# AS5047P.net
KiCad netlist of a schematic drawn in EAGLE
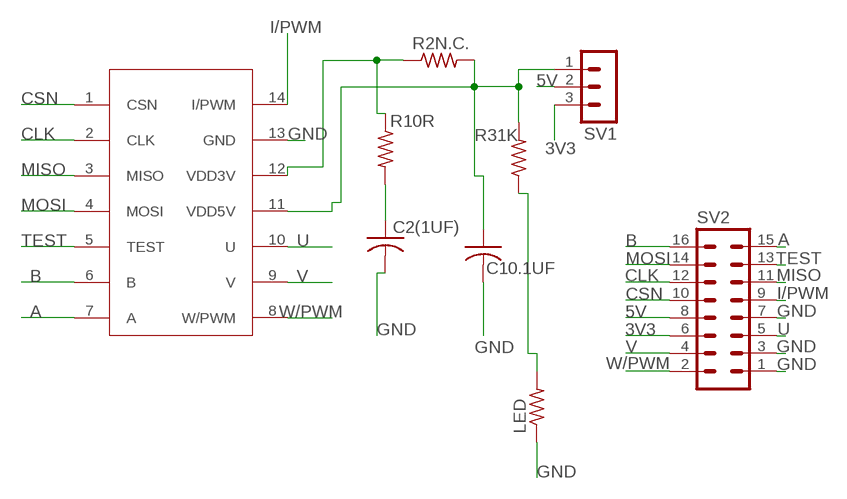
[diagram p0: schematic, sheet 1]

(export (version "E")
  (design (tool "Eeschema 10.0.6"))
  (components
    (comp (ref "C2(1UF)")
      (value "C-USC1206")
      (footprint "eagle-import:C1206")
      (libsource (lib "eagle-import") (part "C-USC1206"))
    )
    (comp (ref "C10.1UF")
      (value "C-USC1206")
      (footprint "eagle-import:C1206")
      (libsource (lib "eagle-import") (part "C-USC1206"))
    )
    (comp (ref "LED")
      (value "R-US_R1206")
      (footprint "eagle-import:R1206")
      (libsource (lib "eagle-import") (part "R-US_R1206"))
    )
    (comp (ref "R2N.C.")
      (value "R-US_R1206")
      (footprint "eagle-import:R1206")
      (libsource (lib "eagle-import") (part "R-US_R1206"))
    )
    (comp (ref "R10R")
      (value "R-US_R1206")
      (footprint "eagle-import:R1206")
      (libsource (lib "eagle-import") (part "R-US_R1206"))
    )
    (comp (ref "R31K")
      (value "R-US_R1206")
      (footprint "eagle-import:R1206")
      (libsource (lib "eagle-import") (part "R-US_R1206"))
    )
    (comp (ref "SV1")
      (value "MA03-1")
      (footprint "eagle-import:MA03-1")
      (libsource (lib "eagle-import") (part "MA03-1"))
    )
    (comp (ref "SV2")
      (value "MA08-2")
      (footprint "eagle-import:MA08-2")
      (libsource (lib "eagle-import") (part "MA08-2"))
    )
    (comp (ref "U$1")
      (value "AS5047")
      (footprint "eagle-import:SOP65P640X110-14N")
      (libsource (lib "eagle-import") (part "AS5047"))
    )
  )
  (nets
    (net (code "1") (name "/3V3") (class "Default")
      (node (ref "SV1") (pin "3") (pinfunction "3_3") (pintype "passive"))
      (node (ref "SV2") (pin "6") (pinfunction "6_6") (pintype "passive"))
    )
    (net (code "2") (name "/5V") (class "Default")
      (node (ref "SV1") (pin "2") (pinfunction "2_2") (pintype "passive"))
      (node (ref "SV2") (pin "8") (pinfunction "8_8") (pintype "passive"))
    )
    (net (code "3") (name "/A") (class "Default")
      (node (ref "SV2") (pin "15") (pinfunction "15_15") (pintype "passive"))
      (node (ref "U$1") (pin "7") (pinfunction "A_7") (pintype "bidirectional"))
    )
    (net (code "4") (name "/B") (class "Default")
      (node (ref "SV2") (pin "16") (pinfunction "16_16") (pintype "passive"))
      (node (ref "U$1") (pin "6") (pinfunction "B_6") (pintype "bidirectional"))
    )
    (net (code "5") (name "/CLK") (class "Default")
      (node (ref "SV2") (pin "12") (pinfunction "12_12") (pintype "passive"))
      (node (ref "U$1") (pin "2") (pinfunction "CLK_2") (pintype "bidirectional"))
    )
    (net (code "6") (name "/CSN") (class "Default")
      (node (ref "SV2") (pin "10") (pinfunction "10_10") (pintype "passive"))
      (node (ref "U$1") (pin "1") (pinfunction "CSN_1") (pintype "bidirectional"))
    )
    (net (code "7") (name "/GND") (class "Default")
      (node (ref "C10.1UF") (pin "2") (pinfunction "2_2") (pintype "passive"))
      (node (ref "C2(1UF)") (pin "2") (pinfunction "2_2") (pintype "passive"))
      (node (ref "LED") (pin "1") (pinfunction "1_1") (pintype "passive"))
      (node (ref "SV2") (pin "1") (pinfunction "1_1") (pintype "passive"))
      (node (ref "SV2") (pin "3") (pinfunction "3_3") (pintype "passive"))
      (node (ref "SV2") (pin "7") (pinfunction "7_7") (pintype "passive"))
      (node (ref "U$1") (pin "13") (pinfunction "GND_13") (pintype "bidirectional"))
    )
    (net (code "8") (name "/I{slash}PWM") (class "Default")
      (node (ref "SV2") (pin "9") (pinfunction "9_9") (pintype "passive"))
      (node (ref "U$1") (pin "14") (pinfunction "I/PWM_14") (pintype "bidirectional"))
    )
    (net (code "9") (name "/MISO") (class "Default")
      (node (ref "SV2") (pin "11") (pinfunction "11_11") (pintype "passive"))
      (node (ref "U$1") (pin "3") (pinfunction "MISO_3") (pintype "bidirectional"))
    )
    (net (code "10") (name "/MOSI") (class "Default")
      (node (ref "SV2") (pin "14") (pinfunction "14_14") (pintype "passive"))
      (node (ref "U$1") (pin "4") (pinfunction "MOSI_4") (pintype "bidirectional"))
    )
    (net (code "11") (name "/TEST") (class "Default")
      (node (ref "SV2") (pin "13") (pinfunction "13_13") (pintype "passive"))
      (node (ref "U$1") (pin "5") (pinfunction "TEST_5") (pintype "bidirectional"))
    )
    (net (code "12") (name "/U") (class "Default")
      (node (ref "SV2") (pin "5") (pinfunction "5_5") (pintype "passive"))
      (node (ref "U$1") (pin "10") (pinfunction "U_10") (pintype "bidirectional"))
    )
    (net (code "13") (name "/V") (class "Default")
      (node (ref "SV2") (pin "4") (pinfunction "4_4") (pintype "passive"))
      (node (ref "U$1") (pin "9") (pinfunction "V_9") (pintype "bidirectional"))
    )
    (net (code "14") (name "/W{slash}PWM") (class "Default")
      (node (ref "SV2") (pin "2") (pinfunction "2_2") (pintype "passive"))
      (node (ref "U$1") (pin "8") (pinfunction "W/PWM_8") (pintype "bidirectional"))
    )
    (net (code "15") (name "Net-(C2(1UF)-Pad1)") (class "Default")
      (node (ref "C2(1UF)") (pin "1") (pinfunction "1_1") (pintype "passive"))
      (node (ref "R10R") (pin "2") (pinfunction "2_2") (pintype "passive"))
    )
    (net (code "16") (name "Net-(LED-Pad2)") (class "Default")
      (node (ref "LED") (pin "2") (pinfunction "2_2") (pintype "passive"))
      (node (ref "R31K") (pin "1") (pinfunction "1_1") (pintype "passive"))
    )
    (net (code "17") (name "Net-(U$1-VDD3V)") (class "Default")
      (node (ref "R10R") (pin "1") (pinfunction "1_1") (pintype "passive"))
      (node (ref "R2N.C.") (pin "1") (pinfunction "1_1") (pintype "passive"))
      (node (ref "U$1") (pin "12") (pinfunction "VDD3V_12") (pintype "bidirectional"))
    )
    (net (code "18") (name "Net-(U$1-VDD5V)") (class "Default")
      (node (ref "C10.1UF") (pin "1") (pinfunction "1_1") (pintype "passive"))
      (node (ref "R2N.C.") (pin "2") (pinfunction "2_2") (pintype "passive"))
      (node (ref "R31K") (pin "2") (pinfunction "2_2") (pintype "passive"))
      (node (ref "SV1") (pin "1") (pinfunction "1_1") (pintype "passive"))
      (node (ref "U$1") (pin "11") (pinfunction "VDD5V_11") (pintype "bidirectional"))
    )
  )
)
